# FeedbackShieldV4_1.net
KiCad netlist of a schematic drawn in EAGLE
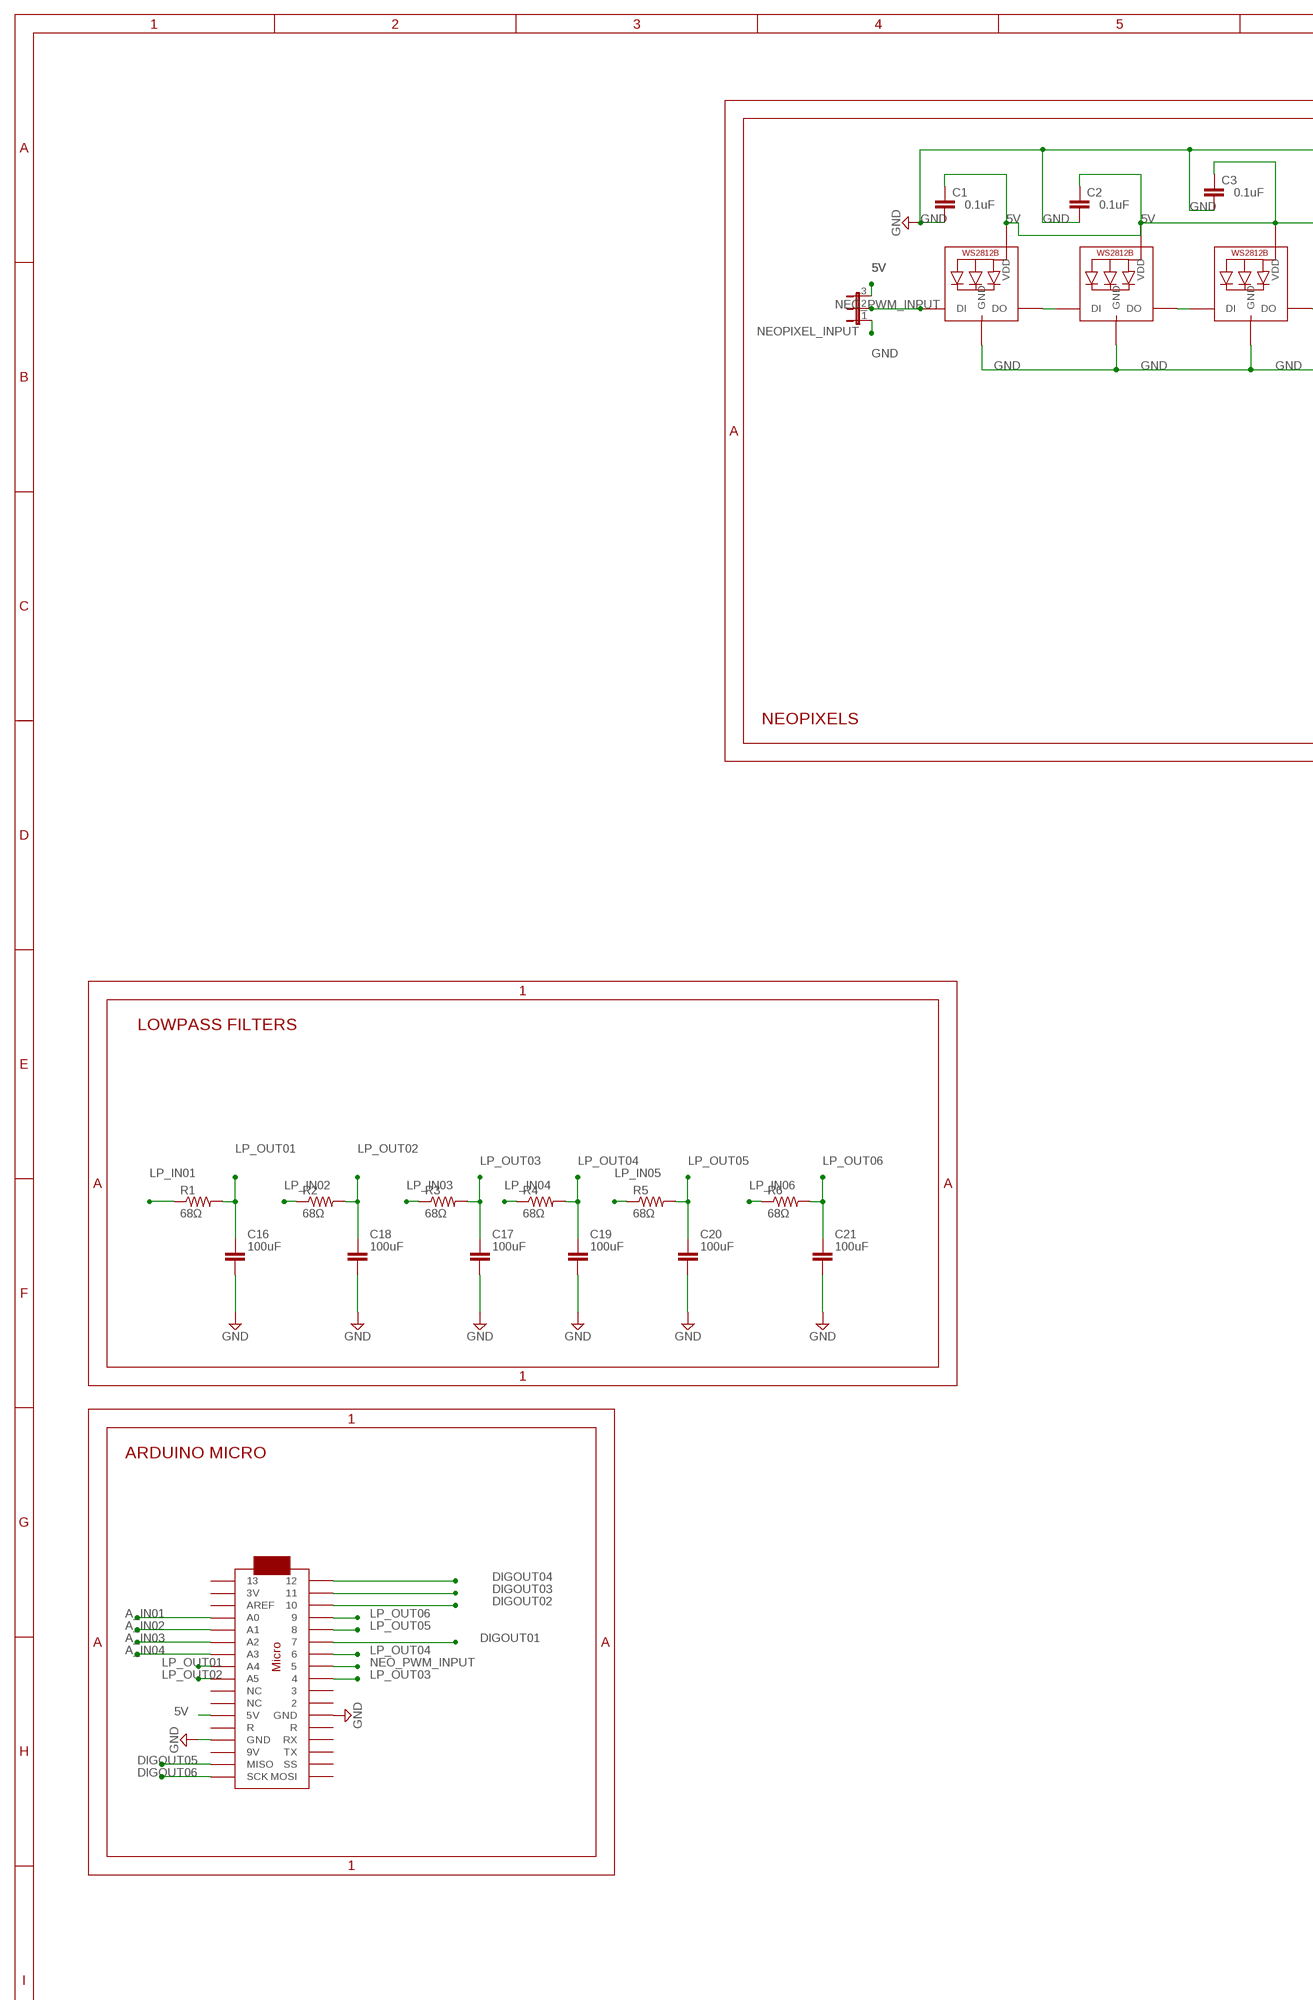
[diagram p0: schematic, sheet 1, part 1 of 2]
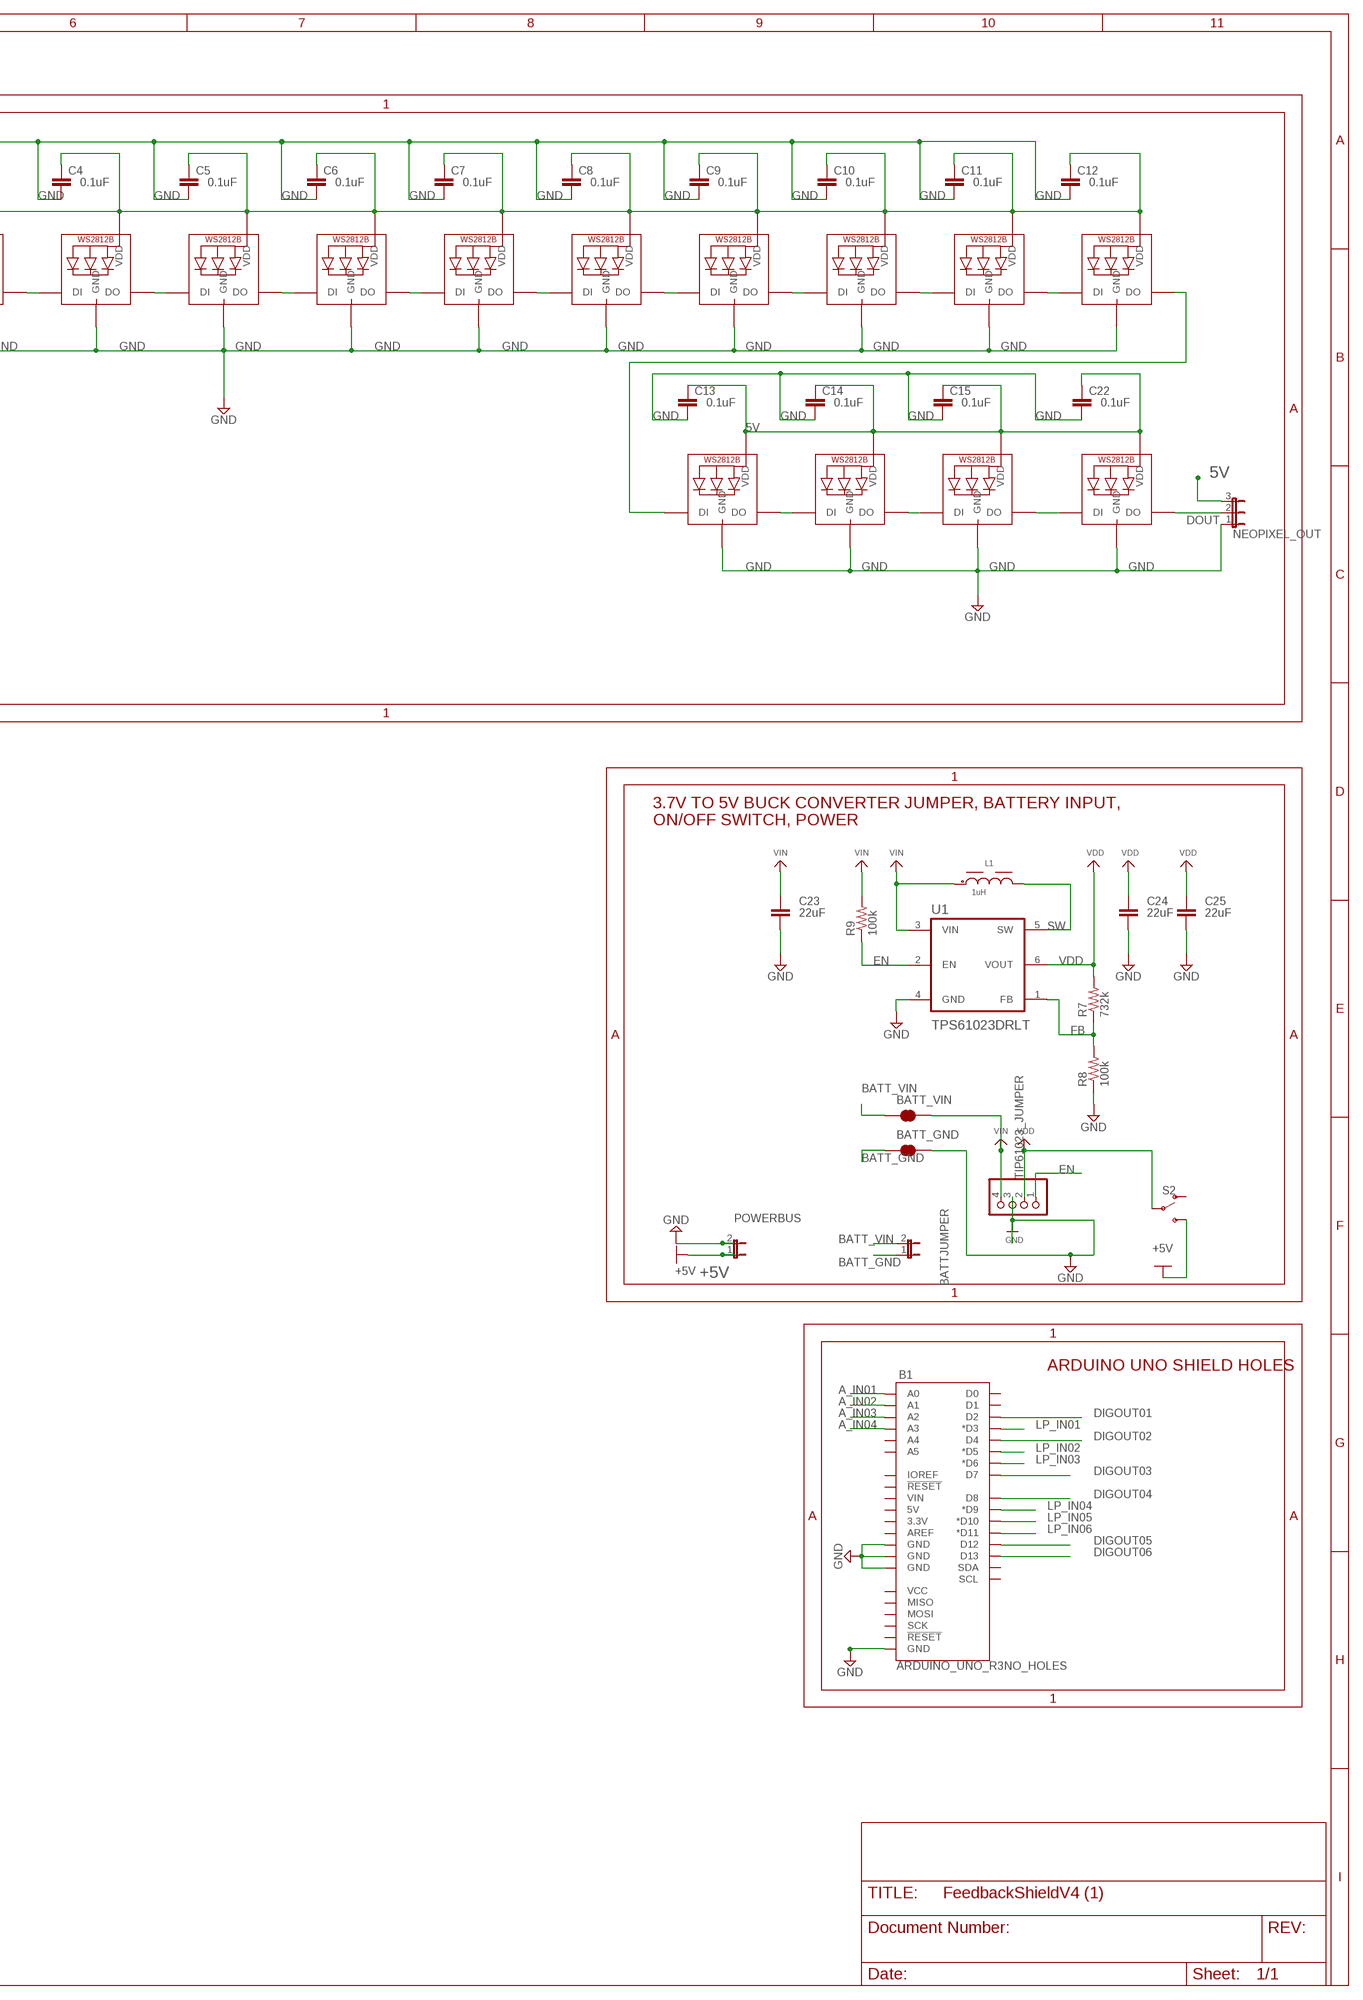
[diagram p1: schematic, sheet 1, part 2 of 2]

(export (version "E")
  (design (tool "Eeschema 10.0.6"))
  (components
    (comp (ref "B1")
      (value "ARDUINO_UNO_R3NO_HOLES")
      (footprint "eagle-import:ARDUINO_R3_NO_HOLES")
      (libsource (lib "eagle-import") (part "ARDUINO_UNO_R3NO_HOLES"))
    )
    (comp (ref "BATTJUMPER")
      (value "JP1E")
      (footprint "eagle-import:JP1")
      (libsource (lib "eagle-import") (part "JP1E"))
    )
    (comp (ref "BATT_GND")
      (value "JUMPER-SMT_2_NC_TRACE_SILK")
      (footprint "eagle-import:SMT-JUMPER_2_NC_TRACE_SILK")
      (libsource (lib "eagle-import") (part "JUMPER-SMT_2_NC_TRACE_SILK"))
    )
    (comp (ref "BATT_VIN")
      (value "JUMPER-SMT_2_NC_TRACE_SILK")
      (footprint "eagle-import:SMT-JUMPER_2_NC_TRACE_SILK")
      (libsource (lib "eagle-import") (part "JUMPER-SMT_2_NC_TRACE_SILK"))
    )
    (comp (ref "C1")
      (value "0.1uF")
      (footprint "eagle-import:CAPC1608X85")
      (libsource (lib "eagle-import") (part "Tutorial - Fusion 360_CCHIP-0603(1608-METRIC)_"))
    )
    (comp (ref "C2")
      (value "0.1uF")
      (footprint "eagle-import:CAPC1608X85")
      (libsource (lib "eagle-import") (part "Tutorial - Fusion 360_CCHIP-0603(1608-METRIC)_"))
    )
    (comp (ref "C3")
      (value "0.1uF")
      (footprint "eagle-import:CAPC1608X85")
      (libsource (lib "eagle-import") (part "Tutorial - Fusion 360_CCHIP-0603(1608-METRIC)_"))
    )
    (comp (ref "C4")
      (value "0.1uF")
      (footprint "eagle-import:CAPC1608X85")
      (libsource (lib "eagle-import") (part "Tutorial - Fusion 360_CCHIP-0603(1608-METRIC)_"))
    )
    (comp (ref "C5")
      (value "0.1uF")
      (footprint "eagle-import:CAPC1608X85")
      (libsource (lib "eagle-import") (part "Tutorial - Fusion 360_CCHIP-0603(1608-METRIC)_"))
    )
    (comp (ref "C6")
      (value "0.1uF")
      (footprint "eagle-import:CAPC1608X85")
      (libsource (lib "eagle-import") (part "Tutorial - Fusion 360_CCHIP-0603(1608-METRIC)_"))
    )
    (comp (ref "C7")
      (value "0.1uF")
      (footprint "eagle-import:CAPC1608X85")
      (libsource (lib "eagle-import") (part "Tutorial - Fusion 360_CCHIP-0603(1608-METRIC)_"))
    )
    (comp (ref "C8")
      (value "0.1uF")
      (footprint "eagle-import:CAPC1608X85")
      (libsource (lib "eagle-import") (part "Tutorial - Fusion 360_CCHIP-0603(1608-METRIC)_"))
    )
    (comp (ref "C9")
      (value "0.1uF")
      (footprint "eagle-import:CAPC1608X85")
      (libsource (lib "eagle-import") (part "Tutorial - Fusion 360_CCHIP-0603(1608-METRIC)_"))
    )
    (comp (ref "C10")
      (value "0.1uF")
      (footprint "eagle-import:CAPC1608X85")
      (libsource (lib "eagle-import") (part "Tutorial - Fusion 360_CCHIP-0603(1608-METRIC)_"))
    )
    (comp (ref "C11")
      (value "0.1uF")
      (footprint "eagle-import:CAPC1608X85")
      (libsource (lib "eagle-import") (part "Tutorial - Fusion 360_CCHIP-0603(1608-METRIC)_"))
    )
    (comp (ref "C12")
      (value "0.1uF")
      (footprint "eagle-import:CAPC1608X85")
      (libsource (lib "eagle-import") (part "Tutorial - Fusion 360_CCHIP-0603(1608-METRIC)_"))
    )
    (comp (ref "C13")
      (value "0.1uF")
      (footprint "eagle-import:CAPC1608X85")
      (libsource (lib "eagle-import") (part "Tutorial - Fusion 360_CCHIP-0603(1608-METRIC)_"))
    )
    (comp (ref "C14")
      (value "0.1uF")
      (footprint "eagle-import:CAPC1608X85")
      (libsource (lib "eagle-import") (part "Tutorial - Fusion 360_CCHIP-0603(1608-METRIC)_"))
    )
    (comp (ref "C15")
      (value "0.1uF")
      (footprint "eagle-import:CAPC1608X85")
      (libsource (lib "eagle-import") (part "Tutorial - Fusion 360_CCHIP-0603(1608-METRIC)_"))
    )
    (comp (ref "C16")
      (value "100uF")
      (footprint "eagle-import:CAPC3216X135")
      (libsource (lib "eagle-import") (part "CCHIP-1206(3216-METRIC)_"))
    )
    (comp (ref "C17")
      (value "100uF")
      (footprint "eagle-import:CAPC3216X135")
      (libsource (lib "eagle-import") (part "CCHIP-1206(3216-METRIC)_"))
    )
    (comp (ref "C18")
      (value "100uF")
      (footprint "eagle-import:CAPC3216X135")
      (libsource (lib "eagle-import") (part "CCHIP-1206(3216-METRIC)_"))
    )
    (comp (ref "C19")
      (value "100uF")
      (footprint "eagle-import:CAPC3216X135")
      (libsource (lib "eagle-import") (part "CCHIP-1206(3216-METRIC)_"))
    )
    (comp (ref "C20")
      (value "100uF")
      (footprint "eagle-import:CAPC3216X135")
      (libsource (lib "eagle-import") (part "CCHIP-1206(3216-METRIC)_"))
    )
    (comp (ref "C21")
      (value "100uF")
      (footprint "eagle-import:CAPC3216X135")
      (libsource (lib "eagle-import") (part "CCHIP-1206(3216-METRIC)_"))
    )
    (comp (ref "C22")
      (value "0.1uF")
      (footprint "eagle-import:CAPC1608X85")
      (libsource (lib "eagle-import") (part "Tutorial - Fusion 360_CCHIP-0603(1608-METRIC)_"))
    )
    (comp (ref "C23")
      (value "22uF")
      (footprint "eagle-import:CAPC2012X110")
      (libsource (lib "eagle-import") (part "Tutorial - Fusion 360_CCHIP-0805(2012-METRIC)_"))
    )
    (comp (ref "C24")
      (value "22uF")
      (footprint "eagle-import:CAPC2012X110")
      (libsource (lib "eagle-import") (part "Tutorial - Fusion 360_CCHIP-0805(2012-METRIC)_"))
    )
    (comp (ref "C25")
      (value "22uF")
      (footprint "eagle-import:CAPC2012X110")
      (libsource (lib "eagle-import") (part "Tutorial - Fusion 360_CCHIP-0805(2012-METRIC)_"))
    )
    (comp (ref "L1")
      (value "1uH")
      (footprint "eagle-import:WE-MAPI_4020")
      (libsource (lib "eagle-import") (part "WE-MAPI_4020_744383560033"))
    )
    (comp (ref "MICRO")
      (value "ARDUINOMICRO")
      (footprint "eagle-import:ARDUINOMICRO")
      (libsource (lib "eagle-import") (part "ARDUINOMICRO"))
    )
    (comp (ref "NEOPIXEL_INPUT")
      (value "JP2E")
      (footprint "eagle-import:JP2")
      (libsource (lib "eagle-import") (part "JP2E"))
    )
    (comp (ref "NEOPIXEL_OUT")
      (value "JP2E")
      (footprint "eagle-import:JP2")
      (libsource (lib "eagle-import") (part "JP2E"))
    )
    (comp (ref "PIN2")
      (value "WS2812B3535")
      (footprint "eagle-import:LED3535")
      (libsource (lib "eagle-import") (part "WS2812B3535"))
    )
    (comp (ref "PIN3")
      (value "WS2812B3535")
      (footprint "eagle-import:LED3535")
      (libsource (lib "eagle-import") (part "WS2812B3535"))
    )
    (comp (ref "PIN4")
      (value "WS2812B3535")
      (footprint "eagle-import:LED3535")
      (libsource (lib "eagle-import") (part "WS2812B3535"))
    )
    (comp (ref "PIN5")
      (value "WS2812B3535")
      (footprint "eagle-import:LED3535")
      (libsource (lib "eagle-import") (part "WS2812B3535"))
    )
    (comp (ref "PIN6")
      (value "WS2812B3535")
      (footprint "eagle-import:LED3535")
      (libsource (lib "eagle-import") (part "WS2812B3535"))
    )
    (comp (ref "PIN7")
      (value "WS2812B3535")
      (footprint "eagle-import:LED3535")
      (libsource (lib "eagle-import") (part "WS2812B3535"))
    )
    (comp (ref "PIN8")
      (value "WS2812B3535")
      (footprint "eagle-import:LED3535")
      (libsource (lib "eagle-import") (part "WS2812B3535"))
    )
    (comp (ref "PIN9")
      (value "WS2812B3535")
      (footprint "eagle-import:LED3535")
      (libsource (lib "eagle-import") (part "WS2812B3535"))
    )
    (comp (ref "PIN10")
      (value "WS2812B3535")
      (footprint "eagle-import:LED3535")
      (libsource (lib "eagle-import") (part "WS2812B3535"))
    )
    (comp (ref "PIN11")
      (value "WS2812B3535")
      (footprint "eagle-import:LED3535")
      (libsource (lib "eagle-import") (part "WS2812B3535"))
    )
    (comp (ref "PIN12")
      (value "WS2812B3535")
      (footprint "eagle-import:LED3535")
      (libsource (lib "eagle-import") (part "WS2812B3535"))
    )
    (comp (ref "PIN13")
      (value "WS2812B3535")
      (footprint "eagle-import:LED3535")
      (libsource (lib "eagle-import") (part "WS2812B3535"))
    )
    (comp (ref "PINA0")
      (value "WS2812B3535")
      (footprint "eagle-import:LED3535")
      (libsource (lib "eagle-import") (part "WS2812B3535"))
    )
    (comp (ref "PINA1")
      (value "WS2812B3535")
      (footprint "eagle-import:LED3535")
      (libsource (lib "eagle-import") (part "WS2812B3535"))
    )
    (comp (ref "PINA2")
      (value "WS2812B3535")
      (footprint "eagle-import:LED3535")
      (libsource (lib "eagle-import") (part "WS2812B3535"))
    )
    (comp (ref "PINA3")
      (value "WS2812B3535")
      (footprint "eagle-import:LED3535")
      (libsource (lib "eagle-import") (part "WS2812B3535"))
    )
    (comp (ref "POWERBUS")
      (value "JP1E")
      (footprint "eagle-import:JP1")
      (libsource (lib "eagle-import") (part "JP1E"))
    )
    (comp (ref "R1")
      (value "68Ω")
      (footprint "eagle-import:RESC2012X65")
      (libsource (lib "eagle-import") (part "R-USCHIP-0805(2012-METRIC)_"))
    )
    (comp (ref "R2")
      (value "68Ω")
      (footprint "eagle-import:RESC2012X65")
      (libsource (lib "eagle-import") (part "R-USCHIP-0805(2012-METRIC)_"))
    )
    (comp (ref "R3")
      (value "68Ω")
      (footprint "eagle-import:RESC2012X65")
      (libsource (lib "eagle-import") (part "R-USCHIP-0805(2012-METRIC)_"))
    )
    (comp (ref "R4")
      (value "68Ω")
      (footprint "eagle-import:RESC2012X65")
      (libsource (lib "eagle-import") (part "R-USCHIP-0805(2012-METRIC)_"))
    )
    (comp (ref "R5")
      (value "68Ω")
      (footprint "eagle-import:RESC2012X65")
      (libsource (lib "eagle-import") (part "R-USCHIP-0805(2012-METRIC)_"))
    )
    (comp (ref "R6")
      (value "68Ω")
      (footprint "eagle-import:RESC2012X65")
      (libsource (lib "eagle-import") (part "R-USCHIP-0805(2012-METRIC)_"))
    )
    (comp (ref "R7")
      (value "732k")
      (footprint "eagle-import:RESC2012X65")
      (libsource (lib "eagle-import") (part "R-USCHIP-0805(2012-METRIC)_"))
    )
    (comp (ref "R8")
      (value "100k")
      (footprint "eagle-import:RESC2012X65")
      (libsource (lib "eagle-import") (part "R-USCHIP-0805(2012-METRIC)_"))
    )
    (comp (ref "R9")
      (value "100k")
      (footprint "eagle-import:RESC2012X65")
      (libsource (lib "eagle-import") (part "R-USCHIP-0805(2012-METRIC)_"))
    )
    (comp (ref "S2")
      (value "SWITCH-SPDT-SMD-RIGHT-ANGLE")
      (footprint "eagle-import:SWITCH_SPST_SMD_A")
      (libsource (lib "eagle-import") (part "SWITCH-SPDT-SMD-RIGHT-ANGLE"))
    )
    (comp (ref "TIP61023_JUMPER")
      (value "HEADER-1X4ROUND")
      (footprint "eagle-import:1X04_ROUND")
      (libsource (lib "eagle-import") (part "HEADER-1X4ROUND"))
    )
    (comp (ref "U1")
      (value "TPS61023DRLT")
      (footprint "eagle-import:SOT50P160X60-6N")
      (libsource (lib "eagle-import") (part "TPS61023DRLT"))
    )
  )
  (nets
    (net (code "1") (name "+5V") (class "Default")
      (node (ref "POWERBUS") (pin "1") (pinfunction "1_1") (pintype "passive"))
      (node (ref "S2") (pin "3") (pinfunction "S_3") (pintype "passive"))
    )
    (net (code "2") (name "/5V") (class "Default")
      (node (ref "C1") (pin "1") (pinfunction "1_1") (pintype "passive"))
      (node (ref "C10") (pin "1") (pinfunction "1_1") (pintype "passive"))
      (node (ref "C11") (pin "1") (pinfunction "1_1") (pintype "passive"))
      (node (ref "C12") (pin "1") (pinfunction "1_1") (pintype "passive"))
      (node (ref "C13") (pin "1") (pinfunction "1_1") (pintype "passive"))
      (node (ref "C14") (pin "1") (pinfunction "1_1") (pintype "passive"))
      (node (ref "C15") (pin "1") (pinfunction "1_1") (pintype "passive"))
      (node (ref "C2") (pin "1") (pinfunction "1_1") (pintype "passive"))
      (node (ref "C22") (pin "1") (pinfunction "1_1") (pintype "passive"))
      (node (ref "C3") (pin "1") (pinfunction "1_1") (pintype "passive"))
      (node (ref "C4") (pin "1") (pinfunction "1_1") (pintype "passive"))
      (node (ref "C5") (pin "1") (pinfunction "1_1") (pintype "passive"))
      (node (ref "C6") (pin "1") (pinfunction "1_1") (pintype "passive"))
      (node (ref "C7") (pin "1") (pinfunction "1_1") (pintype "passive"))
      (node (ref "C8") (pin "1") (pinfunction "1_1") (pintype "passive"))
      (node (ref "C9") (pin "1") (pinfunction "1_1") (pintype "passive"))
      (node (ref "MICRO") (pin "P$23") (pinfunction "5V_P$23") (pintype "bidirectional"))
      (node (ref "NEOPIXEL_INPUT") (pin "3") (pinfunction "3_3") (pintype "passive"))
      (node (ref "NEOPIXEL_OUT") (pin "3") (pinfunction "3_3") (pintype "passive"))
      (node (ref "PIN10") (pin "2") (pinfunction "VDD_2") (pintype "power_in"))
      (node (ref "PIN11") (pin "2") (pinfunction "VDD_2") (pintype "power_in"))
      (node (ref "PIN12") (pin "2") (pinfunction "VDD_2") (pintype "power_in"))
      (node (ref "PIN13") (pin "2") (pinfunction "VDD_2") (pintype "power_in"))
      (node (ref "PIN2") (pin "2") (pinfunction "VDD_2") (pintype "power_in"))
      (node (ref "PIN3") (pin "2") (pinfunction "VDD_2") (pintype "power_in"))
      (node (ref "PIN4") (pin "2") (pinfunction "VDD_2") (pintype "power_in"))
      (node (ref "PIN5") (pin "2") (pinfunction "VDD_2") (pintype "power_in"))
      (node (ref "PIN6") (pin "2") (pinfunction "VDD_2") (pintype "power_in"))
      (node (ref "PIN7") (pin "2") (pinfunction "VDD_2") (pintype "power_in"))
      (node (ref "PIN8") (pin "2") (pinfunction "VDD_2") (pintype "power_in"))
      (node (ref "PIN9") (pin "2") (pinfunction "VDD_2") (pintype "power_in"))
      (node (ref "PINA0") (pin "2") (pinfunction "VDD_2") (pintype "power_in"))
      (node (ref "PINA1") (pin "2") (pinfunction "VDD_2") (pintype "power_in"))
      (node (ref "PINA2") (pin "2") (pinfunction "VDD_2") (pintype "power_in"))
      (node (ref "PINA3") (pin "2") (pinfunction "VDD_2") (pintype "power_in"))
    )
    (net (code "3") (name "/A_IN01") (class "Default")
      (node (ref "B1") (pin "A0") (pinfunction "A0_A0") (pintype "bidirectional"))
      (node (ref "MICRO") (pin "P$31") (pinfunction "A0_P$31") (pintype "bidirectional"))
    )
    (net (code "4") (name "/A_IN02") (class "Default")
      (node (ref "B1") (pin "A1") (pinfunction "A1_A1") (pintype "bidirectional"))
      (node (ref "MICRO") (pin "P$30") (pinfunction "A1_P$30") (pintype "bidirectional"))
    )
    (net (code "5") (name "/A_IN03") (class "Default")
      (node (ref "B1") (pin "A2") (pinfunction "A2_A2") (pintype "bidirectional"))
      (node (ref "MICRO") (pin "P$29") (pinfunction "A2_P$29") (pintype "bidirectional"))
    )
    (net (code "6") (name "/A_IN04") (class "Default")
      (node (ref "B1") (pin "A3") (pinfunction "A3_A3") (pintype "bidirectional"))
      (node (ref "MICRO") (pin "P$28") (pinfunction "A3_P$28") (pintype "bidirectional"))
    )
    (net (code "7") (name "/BATT_GND") (class "Default")
      (node (ref "BATTJUMPER") (pin "1") (pinfunction "1_1") (pintype "passive"))
      (node (ref "BATT_GND") (pin "1") (pinfunction "1_1") (pintype "passive"))
    )
    (net (code "8") (name "/BATT_VIN") (class "Default")
      (node (ref "BATTJUMPER") (pin "2") (pinfunction "2_2") (pintype "passive"))
      (node (ref "BATT_VIN") (pin "1") (pinfunction "1_1") (pintype "passive"))
    )
    (net (code "9") (name "/DIGOUT01") (class "Default")
      (node (ref "B1") (pin "D2") (pinfunction "D2_D2") (pintype "bidirectional"))
      (node (ref "MICRO") (pin "P$6") (pinfunction "7_P$6") (pintype "bidirectional"))
    )
    (net (code "10") (name "/DIGOUT02") (class "Default")
      (node (ref "B1") (pin "D4") (pinfunction "D4_D4") (pintype "bidirectional"))
      (node (ref "MICRO") (pin "P$3") (pinfunction "10_P$3") (pintype "bidirectional"))
    )
    (net (code "11") (name "/DIGOUT03") (class "Default")
      (node (ref "B1") (pin "D7") (pinfunction "D7_D7") (pintype "bidirectional"))
      (node (ref "MICRO") (pin "P$2") (pinfunction "11_P$2") (pintype "bidirectional"))
    )
    (net (code "12") (name "/DIGOUT04") (class "Default")
      (node (ref "B1") (pin "D8") (pinfunction "D8_D8") (pintype "bidirectional"))
      (node (ref "MICRO") (pin "P$1") (pinfunction "12_P$1") (pintype "bidirectional"))
    )
    (net (code "13") (name "/DIGOUT05") (class "Default")
      (node (ref "B1") (pin "D12") (pinfunction "D12_D12") (pintype "bidirectional"))
      (node (ref "MICRO") (pin "P$19") (pinfunction "MISO_P$19") (pintype "bidirectional"))
    )
    (net (code "14") (name "/DIGOUT06") (class "Default")
      (node (ref "B1") (pin "D13") (pinfunction "D13_D13") (pintype "bidirectional"))
      (node (ref "MICRO") (pin "P$18") (pinfunction "SCK_P$18") (pintype "bidirectional"))
    )
    (net (code "15") (name "/DOUT") (class "Default")
      (node (ref "NEOPIXEL_OUT") (pin "2") (pinfunction "2_2") (pintype "passive"))
      (node (ref "PINA3") (pin "3") (pinfunction "DO_3") (pintype "output"))
    )
    (net (code "16") (name "/EN") (class "Default")
      (node (ref "R9") (pin "1") (pinfunction "1_1") (pintype "passive"))
      (node (ref "TIP61023_JUMPER") (pin "1") (pinfunction "1_1") (pintype "passive"))
      (node (ref "U1") (pin "2") (pinfunction "EN_2") (pintype "input"))
    )
    (net (code "17") (name "/FB") (class "Default")
      (node (ref "R7") (pin "1") (pinfunction "1_1") (pintype "passive"))
      (node (ref "R8") (pin "2") (pinfunction "2_2") (pintype "passive"))
      (node (ref "U1") (pin "1") (pinfunction "FB_1") (pintype "input"))
    )
    (net (code "18") (name "/LP_IN01") (class "Default")
      (node (ref "B1") (pin "D3") (pinfunction "*D3_D3") (pintype "bidirectional"))
      (node (ref "R1") (pin "1") (pinfunction "1_1") (pintype "passive"))
    )
    (net (code "19") (name "/LP_IN02") (class "Default")
      (node (ref "B1") (pin "D5") (pinfunction "*D5_D5") (pintype "bidirectional"))
      (node (ref "R2") (pin "1") (pinfunction "1_1") (pintype "passive"))
    )
    (net (code "20") (name "/LP_IN03") (class "Default")
      (node (ref "B1") (pin "D6") (pinfunction "*D6_D6") (pintype "bidirectional"))
      (node (ref "R3") (pin "1") (pinfunction "1_1") (pintype "passive"))
    )
    (net (code "21") (name "/LP_IN04") (class "Default")
      (node (ref "B1") (pin "D9") (pinfunction "*D9_D9") (pintype "bidirectional"))
      (node (ref "R4") (pin "1") (pinfunction "1_1") (pintype "passive"))
    )
    (net (code "22") (name "/LP_IN05") (class "Default")
      (node (ref "B1") (pin "D10") (pinfunction "*D10_D10") (pintype "bidirectional"))
      (node (ref "R5") (pin "1") (pinfunction "1_1") (pintype "passive"))
    )
    (net (code "23") (name "/LP_IN06") (class "Default")
      (node (ref "B1") (pin "D11") (pinfunction "*D11_D11") (pintype "bidirectional"))
      (node (ref "R6") (pin "1") (pinfunction "1_1") (pintype "passive"))
    )
    (net (code "24") (name "/LP_OUT01") (class "Default")
      (node (ref "C16") (pin "1") (pinfunction "1_1") (pintype "passive"))
      (node (ref "MICRO") (pin "P$27") (pinfunction "A4_P$27") (pintype "bidirectional"))
      (node (ref "R1") (pin "2") (pinfunction "2_2") (pintype "passive"))
    )
    (net (code "25") (name "/LP_OUT02") (class "Default")
      (node (ref "C18") (pin "1") (pinfunction "1_1") (pintype "passive"))
      (node (ref "MICRO") (pin "P$26") (pinfunction "A5_P$26") (pintype "bidirectional"))
      (node (ref "R2") (pin "2") (pinfunction "2_2") (pintype "passive"))
    )
    (net (code "26") (name "/LP_OUT03") (class "Default")
      (node (ref "C17") (pin "1") (pinfunction "1_1") (pintype "passive"))
      (node (ref "MICRO") (pin "P$9") (pinfunction "4_P$9") (pintype "bidirectional"))
      (node (ref "R3") (pin "2") (pinfunction "2_2") (pintype "passive"))
    )
    (net (code "27") (name "/LP_OUT04") (class "Default")
      (node (ref "C19") (pin "1") (pinfunction "1_1") (pintype "passive"))
      (node (ref "MICRO") (pin "P$7") (pinfunction "6_P$7") (pintype "bidirectional"))
      (node (ref "R4") (pin "2") (pinfunction "2_2") (pintype "passive"))
    )
    (net (code "28") (name "/LP_OUT05") (class "Default")
      (node (ref "C20") (pin "1") (pinfunction "1_1") (pintype "passive"))
      (node (ref "MICRO") (pin "P$5") (pinfunction "8_P$5") (pintype "bidirectional"))
      (node (ref "R5") (pin "2") (pinfunction "2_2") (pintype "passive"))
    )
    (net (code "29") (name "/LP_OUT06") (class "Default")
      (node (ref "C21") (pin "1") (pinfunction "1_1") (pintype "passive"))
      (node (ref "MICRO") (pin "P$4") (pinfunction "9_P$4") (pintype "bidirectional"))
      (node (ref "R6") (pin "2") (pinfunction "2_2") (pintype "passive"))
    )
    (net (code "30") (name "/NEO_PWM_INPUT") (class "Default")
      (node (ref "MICRO") (pin "P$8") (pinfunction "5_P$8") (pintype "bidirectional"))
      (node (ref "NEOPIXEL_INPUT") (pin "2") (pinfunction "2_2") (pintype "passive"))
      (node (ref "PIN2") (pin "1") (pinfunction "DI_1") (pintype "input"))
    )
    (net (code "31") (name "/SW") (class "Default")
      (node (ref "L1") (pin "2") (pinfunction "2_2") (pintype "passive"))
      (node (ref "U1") (pin "5") (pinfunction "SW_5") (pintype "bidirectional"))
    )
    (net (code "32") (name "GND") (class "Default")
      (node (ref "B1") (pin "GND@1") (pinfunction "GND_GND@1") (pintype "bidirectional"))
      (node (ref "B1") (pin "GND@2") (pinfunction "GND_GND@2") (pintype "bidirectional"))
      (node (ref "B1") (pin "GND@3") (pinfunction "GND_GND@3") (pintype "bidirectional"))
      (node (ref "B1") (pin "GND@4") (pinfunction "GND_GND@4") (pintype "bidirectional"))
      (node (ref "BATT_GND") (pin "2") (pinfunction "2_2") (pintype "passive"))
      (node (ref "C1") (pin "2") (pinfunction "2_2") (pintype "passive"))
      (node (ref "C10") (pin "2") (pinfunction "2_2") (pintype "passive"))
      (node (ref "C11") (pin "2") (pinfunction "2_2") (pintype "passive"))
      (node (ref "C12") (pin "2") (pinfunction "2_2") (pintype "passive"))
      (node (ref "C13") (pin "2") (pinfunction "2_2") (pintype "passive"))
      (node (ref "C14") (pin "2") (pinfunction "2_2") (pintype "passive"))
      (node (ref "C15") (pin "2") (pinfunction "2_2") (pintype "passive"))
      (node (ref "C16") (pin "2") (pinfunction "2_2") (pintype "passive"))
      (node (ref "C17") (pin "2") (pinfunction "2_2") (pintype "passive"))
      (node (ref "C18") (pin "2") (pinfunction "2_2") (pintype "passive"))
      (node (ref "C19") (pin "2") (pinfunction "2_2") (pintype "passive"))
      (node (ref "C2") (pin "2") (pinfunction "2_2") (pintype "passive"))
      (node (ref "C20") (pin "2") (pinfunction "2_2") (pintype "passive"))
      (node (ref "C21") (pin "2") (pinfunction "2_2") (pintype "passive"))
      (node (ref "C22") (pin "2") (pinfunction "2_2") (pintype "passive"))
      (node (ref "C23") (pin "2") (pinfunction "2_2") (pintype "passive"))
      (node (ref "C24") (pin "2") (pinfunction "2_2") (pintype "passive"))
      (node (ref "C25") (pin "2") (pinfunction "2_2") (pintype "passive"))
      (node (ref "C3") (pin "2") (pinfunction "2_2") (pintype "passive"))
      (node (ref "C4") (pin "2") (pinfunction "2_2") (pintype "passive"))
      (node (ref "C5") (pin "2") (pinfunction "2_2") (pintype "passive"))
      (node (ref "C6") (pin "2") (pinfunction "2_2") (pintype "passive"))
      (node (ref "C7") (pin "2") (pinfunction "2_2") (pintype "passive"))
      (node (ref "C8") (pin "2") (pinfunction "2_2") (pintype "passive"))
      (node (ref "C9") (pin "2") (pinfunction "2_2") (pintype "passive"))
      (node (ref "MICRO") (pin "P$12") (pinfunction "GND_P$12") (pintype "bidirectional"))
      (node (ref "MICRO") (pin "P$21") (pinfunction "GND_P$21") (pintype "bidirectional"))
      (node (ref "NEOPIXEL_INPUT") (pin "1") (pinfunction "1_1") (pintype "passive"))
      (node (ref "NEOPIXEL_OUT") (pin "1") (pinfunction "1_1") (pintype "passive"))
      (node (ref "PIN10") (pin "4") (pinfunction "GND_4") (pintype "power_in"))
      (node (ref "PIN11") (pin "4") (pinfunction "GND_4") (pintype "power_in"))
      (node (ref "PIN12") (pin "4") (pinfunction "GND_4") (pintype "power_in"))
      (node (ref "PIN13") (pin "4") (pinfunction "GND_4") (pintype "power_in"))
      (node (ref "PIN2") (pin "4") (pinfunction "GND_4") (pintype "power_in"))
      (node (ref "PIN3") (pin "4") (pinfunction "GND_4") (pintype "power_in"))
      (node (ref "PIN4") (pin "4") (pinfunction "GND_4") (pintype "power_in"))
      (node (ref "PIN5") (pin "4") (pinfunction "GND_4") (pintype "power_in"))
      (node (ref "PIN6") (pin "4") (pinfunction "GND_4") (pintype "power_in"))
      (node (ref "PIN7") (pin "4") (pinfunction "GND_4") (pintype "power_in"))
      (node (ref "PIN8") (pin "4") (pinfunction "GND_4") (pintype "power_in"))
      (node (ref "PIN9") (pin "4") (pinfunction "GND_4") (pintype "power_in"))
      (node (ref "PINA0") (pin "4") (pinfunction "GND_4") (pintype "power_in"))
      (node (ref "PINA1") (pin "4") (pinfunction "GND_4") (pintype "power_in"))
      (node (ref "PINA2") (pin "4") (pinfunction "GND_4") (pintype "power_in"))
      (node (ref "PINA3") (pin "4") (pinfunction "GND_4") (pintype "power_in"))
      (node (ref "POWERBUS") (pin "2") (pinfunction "2_2") (pintype "passive"))
      (node (ref "R8") (pin "1") (pinfunction "1_1") (pintype "passive"))
      (node (ref "TIP61023_JUMPER") (pin "3") (pinfunction "3_3") (pintype "passive"))
      (node (ref "U1") (pin "4") (pinfunction "GND_4") (pintype "power_in"))
    )
    (net (code "33") (name "Net-(PIN2-DO)") (class "Default")
      (node (ref "PIN2") (pin "3") (pinfunction "DO_3") (pintype "output"))
      (node (ref "PIN3") (pin "1") (pinfunction "DI_1") (pintype "input"))
    )
    (net (code "34") (name "Net-(PIN3-DO)") (class "Default")
      (node (ref "PIN3") (pin "3") (pinfunction "DO_3") (pintype "output"))
      (node (ref "PIN4") (pin "1") (pinfunction "DI_1") (pintype "input"))
    )
    (net (code "35") (name "Net-(PIN4-DO)") (class "Default")
      (node (ref "PIN4") (pin "3") (pinfunction "DO_3") (pintype "output"))
      (node (ref "PIN5") (pin "1") (pinfunction "DI_1") (pintype "input"))
    )
    (net (code "36") (name "Net-(PIN5-DO)") (class "Default")
      (node (ref "PIN5") (pin "3") (pinfunction "DO_3") (pintype "output"))
      (node (ref "PIN6") (pin "1") (pinfunction "DI_1") (pintype "input"))
    )
    (net (code "37") (name "Net-(PIN6-DO)") (class "Default")
      (node (ref "PIN6") (pin "3") (pinfunction "DO_3") (pintype "output"))
      (node (ref "PIN7") (pin "1") (pinfunction "DI_1") (pintype "input"))
    )
    (net (code "38") (name "Net-(PIN7-DO)") (class "Default")
      (node (ref "PIN7") (pin "3") (pinfunction "DO_3") (pintype "output"))
      (node (ref "PIN8") (pin "1") (pinfunction "DI_1") (pintype "input"))
    )
    (net (code "39") (name "Net-(PIN8-DO)") (class "Default")
      (node (ref "PIN8") (pin "3") (pinfunction "DO_3") (pintype "output"))
      (node (ref "PIN9") (pin "1") (pinfunction "DI_1") (pintype "input"))
    )
    (net (code "40") (name "Net-(PIN10-DI)") (class "Default")
      (node (ref "PIN10") (pin "1") (pinfunction "DI_1") (pintype "input"))
      (node (ref "PIN9") (pin "3") (pinfunction "DO_3") (pintype "output"))
    )
    (net (code "41") (name "Net-(PIN10-DO)") (class "Default")
      (node (ref "PIN10") (pin "3") (pinfunction "DO_3") (pintype "output"))
      (node (ref "PIN11") (pin "1") (pinfunction "DI_1") (pintype "input"))
    )
    (net (code "42") (name "Net-(PIN11-DO)") (class "Default")
      (node (ref "PIN11") (pin "3") (pinfunction "DO_3") (pintype "output"))
      (node (ref "PIN12") (pin "1") (pinfunction "DI_1") (pintype "input"))
    )
    (net (code "43") (name "Net-(PIN12-DO)") (class "Default")
      (node (ref "PIN12") (pin "3") (pinfunction "DO_3") (pintype "output"))
      (node (ref "PIN13") (pin "1") (pinfunction "DI_1") (pintype "input"))
    )
    (net (code "44") (name "Net-(PIN13-DO)") (class "Default")
      (node (ref "PIN13") (pin "3") (pinfunction "DO_3") (pintype "output"))
      (node (ref "PINA0") (pin "1") (pinfunction "DI_1") (pintype "input"))
    )
    (net (code "45") (name "Net-(PINA0-DO)") (class "Default")
      (node (ref "PINA0") (pin "3") (pinfunction "DO_3") (pintype "output"))
      (node (ref "PINA1") (pin "1") (pinfunction "DI_1") (pintype "input"))
    )
    (net (code "46") (name "Net-(PINA1-DO)") (class "Default")
      (node (ref "PINA1") (pin "3") (pinfunction "DO_3") (pintype "output"))
      (node (ref "PINA2") (pin "1") (pinfunction "DI_1") (pintype "input"))
    )
    (net (code "47") (name "Net-(PINA2-DO)") (class "Default")
      (node (ref "PINA2") (pin "3") (pinfunction "DO_3") (pintype "output"))
      (node (ref "PINA3") (pin "1") (pinfunction "DI_1") (pintype "input"))
    )
    (net (code "48") (name "VDD") (class "Default")
      (node (ref "C24") (pin "1") (pinfunction "1_1") (pintype "passive"))
      (node (ref "C25") (pin "1") (pinfunction "1_1") (pintype "passive"))
      (node (ref "R7") (pin "2") (pinfunction "2_2") (pintype "passive"))
      (node (ref "S2") (pin "2") (pinfunction "P_2") (pintype "passive"))
      (node (ref "TIP61023_JUMPER") (pin "2") (pinfunction "2_2") (pintype "passive"))
      (node (ref "U1") (pin "6") (pinfunction "VOUT_6") (pintype "output"))
    )
    (net (code "49") (name "VIN") (class "Default")
      (node (ref "BATT_VIN") (pin "2") (pinfunction "2_2") (pintype "passive"))
      (node (ref "C23") (pin "1") (pinfunction "1_1") (pintype "passive"))
      (node (ref "L1") (pin "1") (pinfunction "1_1") (pintype "passive"))
      (node (ref "R9") (pin "2") (pinfunction "2_2") (pintype "passive"))
      (node (ref "TIP61023_JUMPER") (pin "4") (pinfunction "4_4") (pintype "passive"))
      (node (ref "U1") (pin "3") (pinfunction "VIN_3") (pintype "input"))
    )
    (net (code "50") (name "unconnected-(B1-Pad3.3V)") (class "Default")
      (node (ref "B1") (pin "3.3V") (pinfunction "3.3V_3.3V") (pintype "bidirectional"))
    )
    (net (code "51") (name "unconnected-(B1-Pad5V)") (class "Default")
      (node (ref "B1") (pin "5V") (pinfunction "5V_5V") (pintype "bidirectional"))
    )
    (net (code "52") (name "unconnected-(B1-PadA4)") (class "Default")
      (node (ref "B1") (pin "A4") (pinfunction "A4_A4") (pintype "bidirectional"))
    )
    (net (code "53") (name "unconnected-(B1-PadA5)") (class "Default")
      (node (ref "B1") (pin "A5") (pinfunction "A5_A5") (pintype "bidirectional"))
    )
    (net (code "54") (name "unconnected-(B1-PadAREF)") (class "Default")
      (node (ref "B1") (pin "AREF") (pinfunction "AREF_AREF") (pintype "bidirectional"))
    )
    (net (code "55") (name "unconnected-(B1-PadD0)") (class "Default")
      (node (ref "B1") (pin "D0") (pinfunction "D0_D0") (pintype "bidirectional"))
    )
    (net (code "56") (name "unconnected-(B1-PadD1)") (class "Default")
      (node (ref "B1") (pin "D1") (pinfunction "D1_D1") (pintype "bidirectional"))
    )
    (net (code "57") (name "unconnected-(B1-PadIOREF)") (class "Default")
      (node (ref "B1") (pin "IOREF") (pinfunction "IOREF_IOREF") (pintype "bidirectional"))
    )
    (net (code "58") (name "unconnected-(B1-PadMISO)") (class "Default")
      (node (ref "B1") (pin "MISO") (pinfunction "MISO_MISO") (pintype "bidirectional"))
    )
    (net (code "59") (name "unconnected-(B1-PadMOSI)") (class "Default")
      (node (ref "B1") (pin "MOSI") (pinfunction "MOSI_MOSI") (pintype "bidirectional"))
    )
    (net (code "60") (name "unconnected-(B1-PadSCK)") (class "Default")
      (node (ref "B1") (pin "SCK") (pinfunction "SCK_SCK") (pintype "bidirectional"))
    )
    (net (code "61") (name "unconnected-(B1-PadSCL)") (class "Default")
      (node (ref "B1") (pin "SCL") (pinfunction "SCL_SCL") (pintype "bidirectional"))
    )
    (net (code "62") (name "unconnected-(B1-PadSDA)") (class "Default")
      (node (ref "B1") (pin "SDA") (pinfunction "SDA_SDA") (pintype "bidirectional"))
    )
    (net (code "63") (name "unconnected-(B1-PadVCC)") (class "Default")
      (node (ref "B1") (pin "VCC") (pinfunction "VCC_VCC") (pintype "bidirectional"))
    )
    (net (code "64") (name "unconnected-(B1-PadVIN)") (class "Default")
      (node (ref "B1") (pin "VIN") (pinfunction "VIN_VIN") (pintype "bidirectional"))
    )
    (net (code "65") (name "unconnected-(B1-~{RESET}-PadRESET@1)") (class "Default")
      (node (ref "B1") (pin "RESET@1") (pinfunction "~{RESET}_RESET@1") (pintype "bidirectional"))
    )
    (net (code "66") (name "unconnected-(B1-~{RESET}-PadRESET@2)") (class "Default")
      (node (ref "B1") (pin "RESET@2") (pinfunction "~{RESET}_RESET@2") (pintype "bidirectional"))
    )
    (net (code "67") (name "unconnected-(MICRO-2-PadP$11)") (class "Default")
      (node (ref "MICRO") (pin "P$11") (pinfunction "2_P$11") (pintype "bidirectional"))
    )
    (net (code "68") (name "unconnected-(MICRO-3-PadP$10)") (class "Default")
      (node (ref "MICRO") (pin "P$10") (pinfunction "3_P$10") (pintype "bidirectional"))
    )
    (net (code "69") (name "unconnected-(MICRO-3V-PadP$33)") (class "Default")
      (node (ref "MICRO") (pin "P$33") (pinfunction "3V_P$33") (pintype "bidirectional"))
    )
    (net (code "70") (name "unconnected-(MICRO-9V-PadP$20)") (class "Default")
      (node (ref "MICRO") (pin "P$20") (pinfunction "9V_P$20") (pintype "bidirectional"))
    )
    (net (code "71") (name "unconnected-(MICRO-13-PadP$34)") (class "Default")
      (node (ref "MICRO") (pin "P$34") (pinfunction "13_P$34") (pintype "bidirectional"))
    )
    (net (code "72") (name "unconnected-(MICRO-AREF-PadP$32)") (class "Default")
      (node (ref "MICRO") (pin "P$32") (pinfunction "AREF_P$32") (pintype "bidirectional"))
    )
    (net (code "73") (name "unconnected-(MICRO-MOSI-PadP$17)") (class "Default")
      (node (ref "MICRO") (pin "P$17") (pinfunction "MOSI_P$17") (pintype "bidirectional"))
    )
    (net (code "74") (name "unconnected-(MICRO-NC-PadP$24)") (class "Default")
      (node (ref "MICRO") (pin "P$24") (pinfunction "NC_P$24") (pintype "bidirectional"))
    )
    (net (code "75") (name "unconnected-(MICRO-NC-PadP$25)") (class "Default")
      (node (ref "MICRO") (pin "P$25") (pinfunction "NC_P$25") (pintype "bidirectional"))
    )
    (net (code "76") (name "unconnected-(MICRO-R-PadP$13)") (class "Default")
      (node (ref "MICRO") (pin "P$13") (pinfunction "R_P$13") (pintype "bidirectional"))
    )
    (net (code "77") (name "unconnected-(MICRO-R-PadP$22)") (class "Default")
      (node (ref "MICRO") (pin "P$22") (pinfunction "R_P$22") (pintype "bidirectional"))
    )
    (net (code "78") (name "unconnected-(MICRO-RX-PadP$14)") (class "Default")
      (node (ref "MICRO") (pin "P$14") (pinfunction "RX_P$14") (pintype "bidirectional"))
    )
    (net (code "79") (name "unconnected-(MICRO-SS-PadP$16)") (class "Default")
      (node (ref "MICRO") (pin "P$16") (pinfunction "SS_P$16") (pintype "bidirectional"))
    )
    (net (code "80") (name "unconnected-(MICRO-TX-PadP$15)") (class "Default")
      (node (ref "MICRO") (pin "P$15") (pinfunction "TX_P$15") (pintype "bidirectional"))
    )
    (net (code "81") (name "unconnected-(S2-O-Pad1)") (class "Default")
      (node (ref "S2") (pin "1") (pinfunction "O_1") (pintype "passive"))
    )
  )
)
